# ADCduinoModule_Sensor_2.net
KiCad netlist of a schematic drawn in Altium Designer
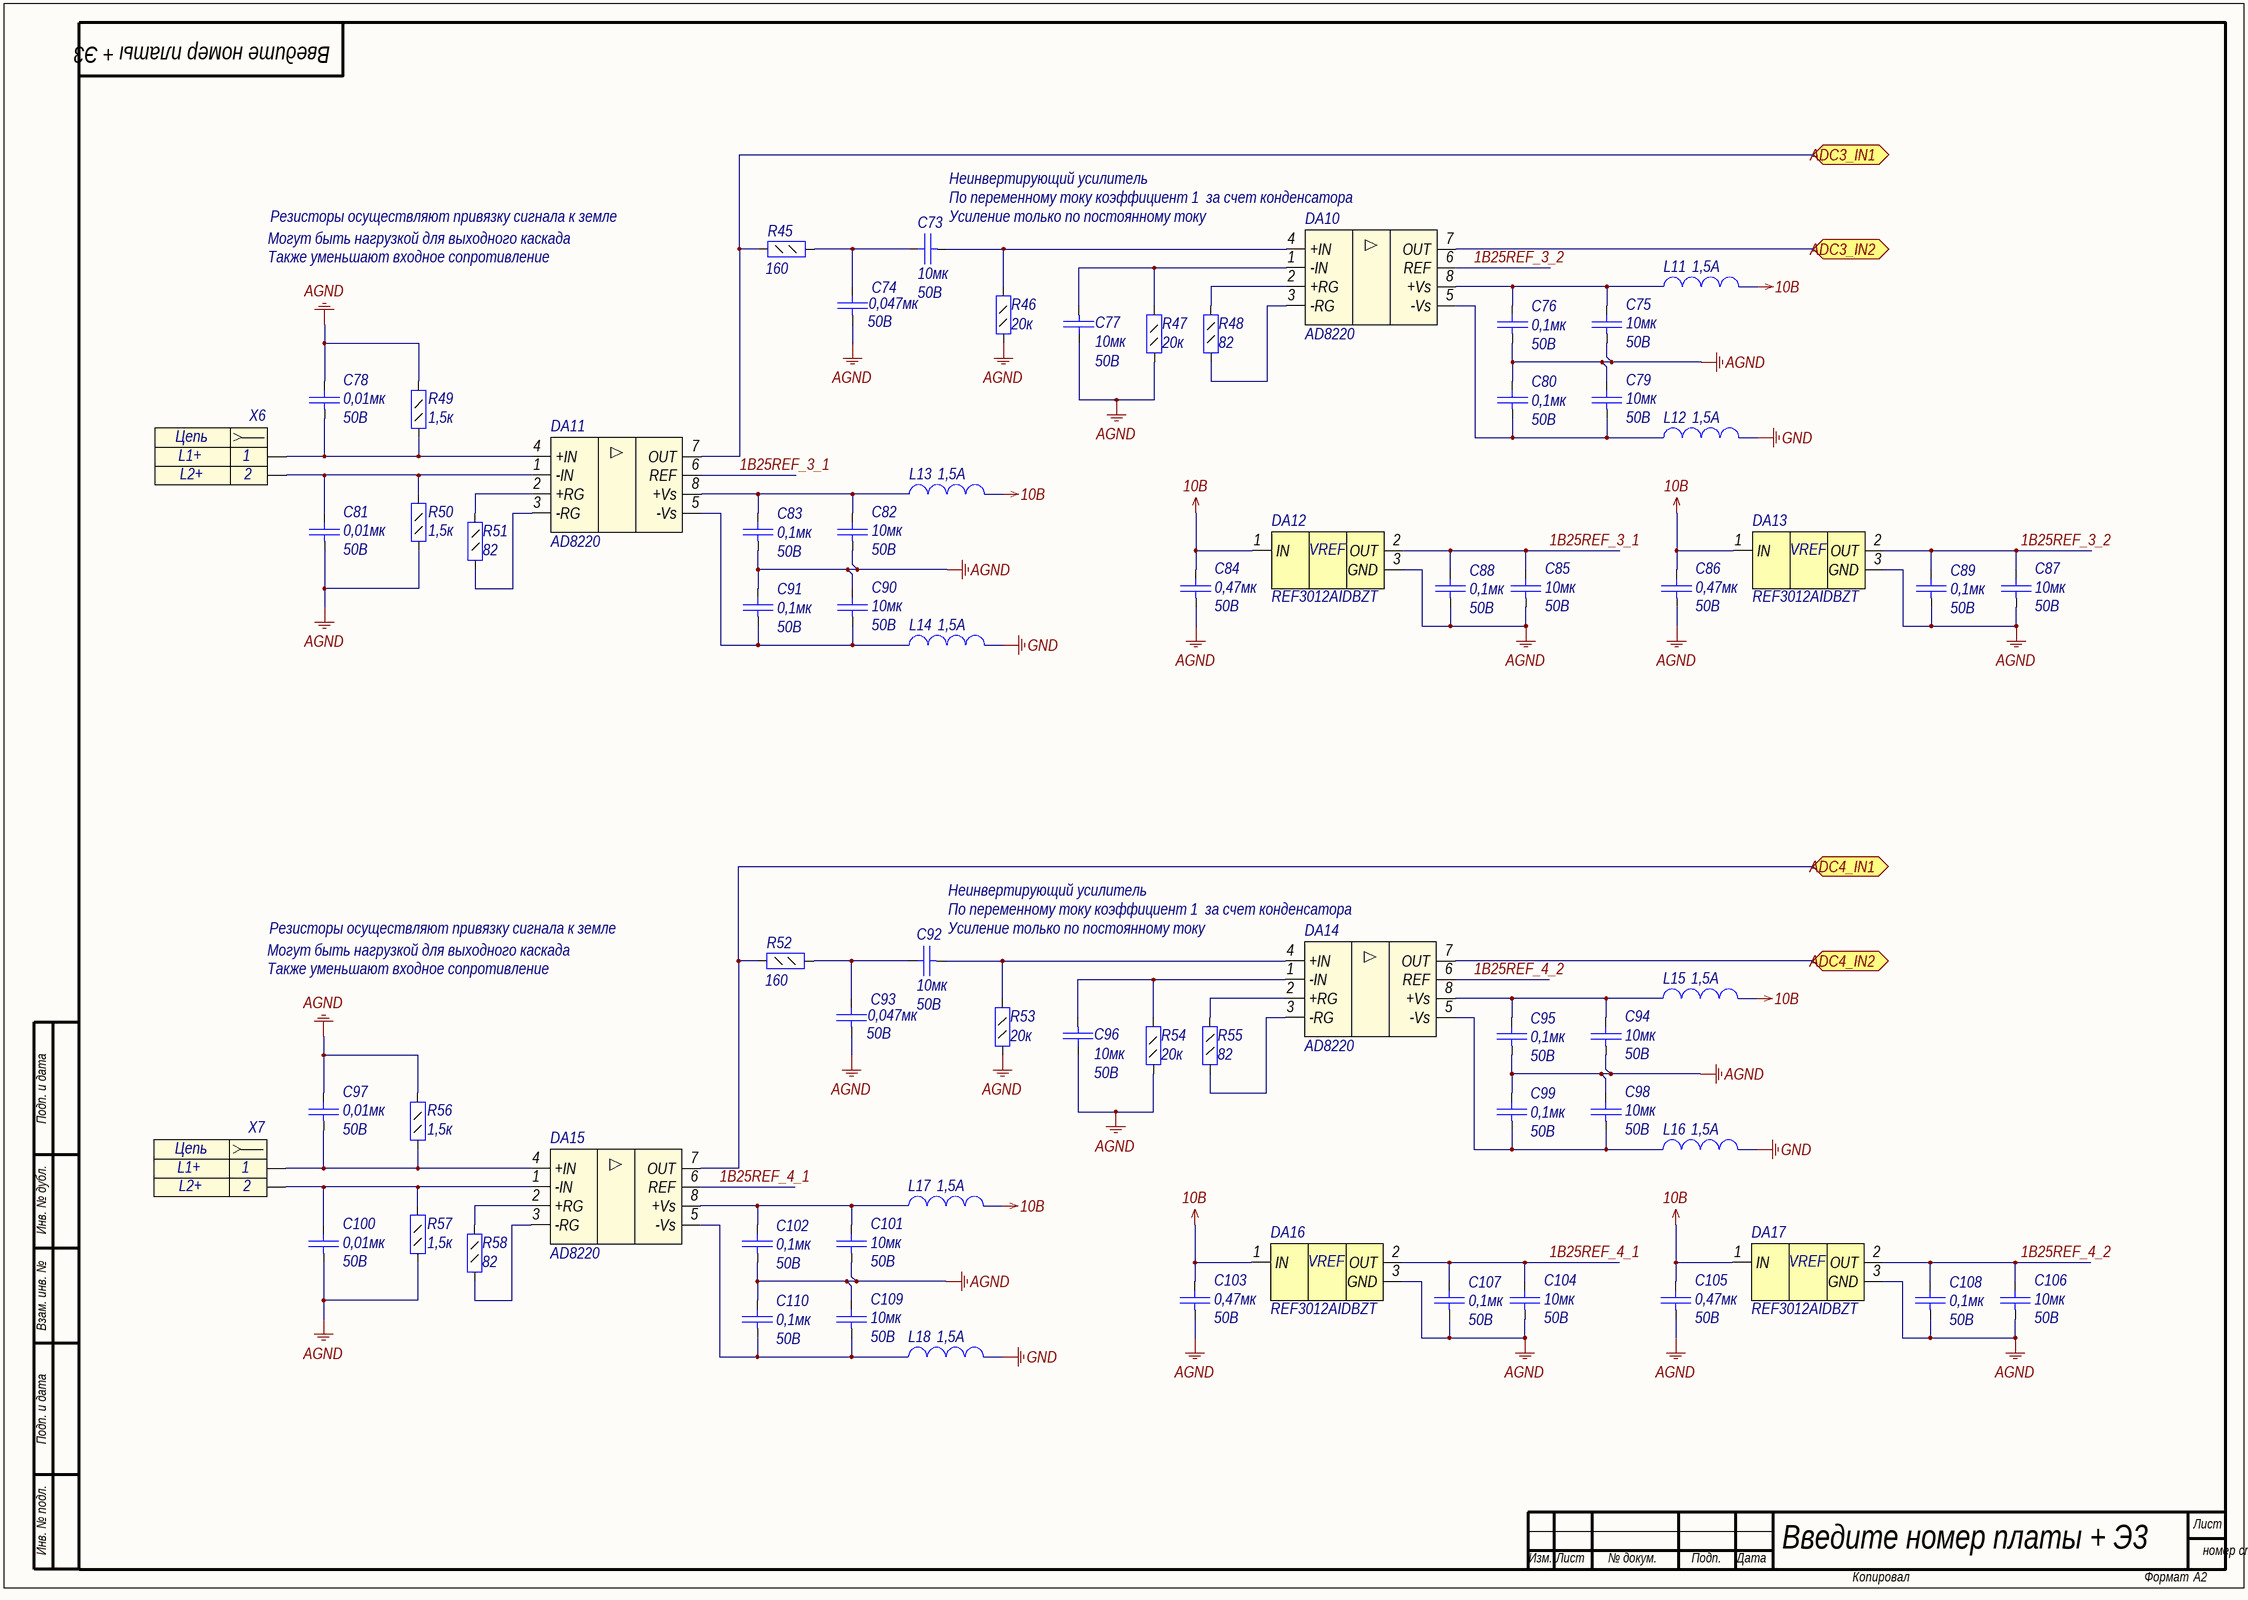
[diagram p0: ADCduinoModule_Sensor_2.SchDoc]

(export (version "E")
  (design (tool "Eeschema 10.0.6"))
  (components
    (comp (ref "C73")
      (value "10мк")
      (footprint "C1210")
      (description "Конденсатор")
      (fields
        (field (name "VOLTAGE") "50В")
        (field (name "PART NUMBER") "GRM32ER71H106K")
        (field (name "Comment") "Capacitor")
      )
      (libsource (lib "MOP44") (part "Capacitor"))
    )
    (comp (ref "C74")
      (value "0,047мк")
      (footprint "C0805")
      (description "Конденсатор")
      (fields
        (field (name "VOLTAGE") "50B")
        (field (name "PART NUMBER") "GRM21BR71H473K")
        (field (name "Comment") "Capacitor")
      )
      (libsource (lib "MOP44") (part "Capacitor"))
    )
    (comp (ref "C75")
      (value "10мк")
      (footprint "C1210")
      (description "Конденсатор")
      (fields
        (field (name "VOLTAGE") "50В")
        (field (name "PART NUMBER") "GRM32ER71H106K")
        (field (name "Comment") "Capacitor")
      )
      (libsource (lib "MOP44") (part "Capacitor"))
    )
    (comp (ref "C76")
      (value "0,1мк")
      (footprint "C0805")
      (description "Конденсатор")
      (fields
        (field (name "VOLTAGE") "50B")
        (field (name "PART NUMBER") "GRM21BR71H104K**")
        (field (name "Comment") "Capacitor")
      )
      (libsource (lib "MOP44") (part "Capacitor"))
    )
    (comp (ref "C77")
      (value "10мк")
      (footprint "C1210")
      (description "Конденсатор")
      (fields
        (field (name "VOLTAGE") "50В")
        (field (name "PART NUMBER") "GRM32ER71H106K")
        (field (name "Comment") "Capacitor")
      )
      (libsource (lib "MOP44") (part "Capacitor"))
    )
    (comp (ref "C78")
      (value "0,01мк")
      (footprint "C0805")
      (description "Конденсатор")
      (fields
        (field (name "VOLTAGE") "50B")
        (field (name "PART NUMBER") "GRM216R71H103K")
        (field (name "Comment") "Capacitor")
      )
      (libsource (lib "MOP44") (part "Capacitor"))
    )
    (comp (ref "C79")
      (value "10мк")
      (footprint "C1210")
      (description "Конденсатор")
      (fields
        (field (name "VOLTAGE") "50В")
        (field (name "PART NUMBER") "GRM32ER71H106K")
        (field (name "Comment") "Capacitor")
      )
      (libsource (lib "MOP44") (part "Capacitor"))
    )
    (comp (ref "C80")
      (value "0,1мк")
      (footprint "C0805")
      (description "Конденсатор")
      (fields
        (field (name "VOLTAGE") "50B")
        (field (name "PART NUMBER") "GRM21BR71H104K**")
        (field (name "Comment") "Capacitor")
      )
      (libsource (lib "MOP44") (part "Capacitor"))
    )
    (comp (ref "C81")
      (value "0,01мк")
      (footprint "C0805")
      (description "Конденсатор")
      (fields
        (field (name "VOLTAGE") "50B")
        (field (name "PART NUMBER") "GRM216R71H103K")
        (field (name "Comment") "Capacitor")
      )
      (libsource (lib "MOP44") (part "Capacitor"))
    )
    (comp (ref "C82")
      (value "10мк")
      (footprint "C1210")
      (description "Конденсатор")
      (fields
        (field (name "VOLTAGE") "50В")
        (field (name "PART NUMBER") "GRM32ER71H106K")
        (field (name "Comment") "Capacitor")
      )
      (libsource (lib "MOP44") (part "Capacitor"))
    )
    (comp (ref "C83")
      (value "0,1мк")
      (footprint "C0805")
      (description "Конденсатор")
      (fields
        (field (name "VOLTAGE") "50B")
        (field (name "PART NUMBER") "GRM21BR71H104K**")
        (field (name "Comment") "Capacitor")
      )
      (libsource (lib "MOP44") (part "Capacitor"))
    )
    (comp (ref "C84")
      (value "0,47мк")
      (footprint "C0805")
      (description "Конденсатор")
      (fields
        (field (name "VOLTAGE") "50B")
        (field (name "PART NUMBER") "GRM219R71C474K")
        (field (name "Comment") "Capacitor")
      )
      (libsource (lib "MOP44") (part "Capacitor"))
    )
    (comp (ref "C85")
      (value "10мк")
      (footprint "C1210")
      (description "Конденсатор")
      (fields
        (field (name "VOLTAGE") "50В")
        (field (name "PART NUMBER") "GRM32ER71H106K")
        (field (name "Comment") "Capacitor")
      )
      (libsource (lib "MOP44") (part "Capacitor"))
    )
    (comp (ref "C86")
      (value "0,47мк")
      (footprint "C0805")
      (description "Конденсатор")
      (fields
        (field (name "VOLTAGE") "50B")
        (field (name "PART NUMBER") "GRM219R71C474K")
        (field (name "Comment") "Capacitor")
      )
      (libsource (lib "MOP44") (part "Capacitor"))
    )
    (comp (ref "C87")
      (value "10мк")
      (footprint "C1210")
      (description "Конденсатор")
      (fields
        (field (name "VOLTAGE") "50В")
        (field (name "PART NUMBER") "GRM32ER71H106K")
        (field (name "Comment") "Capacitor")
      )
      (libsource (lib "MOP44") (part "Capacitor"))
    )
    (comp (ref "C88")
      (value "0,1мк")
      (footprint "C0805")
      (description "Конденсатор")
      (fields
        (field (name "VOLTAGE") "50B")
        (field (name "PART NUMBER") "GRM21BR71H104K**")
        (field (name "Comment") "Capacitor")
      )
      (libsource (lib "MOP44") (part "Capacitor"))
    )
    (comp (ref "C89")
      (value "0,1мк")
      (footprint "C0805")
      (description "Конденсатор")
      (fields
        (field (name "VOLTAGE") "50B")
        (field (name "PART NUMBER") "GRM21BR71H104K**")
        (field (name "Comment") "Capacitor")
      )
      (libsource (lib "MOP44") (part "Capacitor"))
    )
    (comp (ref "C90")
      (value "10мк")
      (footprint "C1210")
      (description "Конденсатор")
      (fields
        (field (name "VOLTAGE") "50В")
        (field (name "PART NUMBER") "GRM32ER71H106K")
        (field (name "Comment") "Capacitor")
      )
      (libsource (lib "MOP44") (part "Capacitor"))
    )
    (comp (ref "C91")
      (value "0,1мк")
      (footprint "C0805")
      (description "Конденсатор")
      (fields
        (field (name "VOLTAGE") "50B")
        (field (name "PART NUMBER") "GRM21BR71H104K**")
        (field (name "Comment") "Capacitor")
      )
      (libsource (lib "MOP44") (part "Capacitor"))
    )
    (comp (ref "C92")
      (value "10мк")
      (footprint "C1210")
      (description "Конденсатор")
      (fields
        (field (name "VOLTAGE") "50В")
        (field (name "PART NUMBER") "GRM32ER71H106K")
        (field (name "Comment") "Capacitor")
      )
      (libsource (lib "MOP44") (part "Capacitor"))
    )
    (comp (ref "C93")
      (value "0,047мк")
      (footprint "C0805")
      (description "Конденсатор")
      (fields
        (field (name "VOLTAGE") "50B")
        (field (name "PART NUMBER") "GRM21BR71H473K")
        (field (name "Comment") "Capacitor")
      )
      (libsource (lib "MOP44") (part "Capacitor"))
    )
    (comp (ref "C94")
      (value "10мк")
      (footprint "C1210")
      (description "Конденсатор")
      (fields
        (field (name "VOLTAGE") "50В")
        (field (name "PART NUMBER") "GRM32ER71H106K")
        (field (name "Comment") "Capacitor")
      )
      (libsource (lib "MOP44") (part "Capacitor"))
    )
    (comp (ref "C95")
      (value "0,1мк")
      (footprint "C0805")
      (description "Конденсатор")
      (fields
        (field (name "VOLTAGE") "50B")
        (field (name "PART NUMBER") "GRM21BR71H104K**")
        (field (name "Comment") "Capacitor")
      )
      (libsource (lib "MOP44") (part "Capacitor"))
    )
    (comp (ref "C96")
      (value "10мк")
      (footprint "C1210")
      (description "Конденсатор")
      (fields
        (field (name "VOLTAGE") "50В")
        (field (name "PART NUMBER") "GRM32ER71H106K")
        (field (name "Comment") "Capacitor")
      )
      (libsource (lib "") (part "Capacitor_1"))
    )
    (comp (ref "C97")
      (value "0,01мк")
      (footprint "C0805")
      (description "Конденсатор")
      (fields
        (field (name "VOLTAGE") "50B")
        (field (name "PART NUMBER") "GRM216R71H103K")
        (field (name "Comment") "Capacitor")
      )
      (libsource (lib "MOP44") (part "Capacitor"))
    )
    (comp (ref "C98")
      (value "10мк")
      (footprint "C1210")
      (description "Конденсатор")
      (fields
        (field (name "VOLTAGE") "50В")
        (field (name "PART NUMBER") "GRM32ER71H106K")
        (field (name "Comment") "Capacitor")
      )
      (libsource (lib "MOP44") (part "Capacitor"))
    )
    (comp (ref "C99")
      (value "0,1мк")
      (footprint "C0805")
      (description "Конденсатор")
      (fields
        (field (name "VOLTAGE") "50B")
        (field (name "PART NUMBER") "GRM21BR71H104K**")
        (field (name "Comment") "Capacitor")
      )
      (libsource (lib "MOP44") (part "Capacitor"))
    )
    (comp (ref "C100")
      (value "0,01мк")
      (footprint "C0805")
      (description "Конденсатор")
      (fields
        (field (name "VOLTAGE") "50B")
        (field (name "PART NUMBER") "GRM216R71H103K")
        (field (name "Comment") "Capacitor")
      )
      (libsource (lib "MOP44") (part "Capacitor"))
    )
    (comp (ref "C101")
      (value "10мк")
      (footprint "C1210")
      (description "Конденсатор")
      (fields
        (field (name "VOLTAGE") "50В")
        (field (name "PART NUMBER") "GRM32ER71H106K")
        (field (name "Comment") "Capacitor")
      )
      (libsource (lib "MOP44") (part "Capacitor"))
    )
    (comp (ref "C102")
      (value "0,1мк")
      (footprint "C0805")
      (description "Конденсатор")
      (fields
        (field (name "VOLTAGE") "50B")
        (field (name "PART NUMBER") "GRM21BR71H104K**")
        (field (name "Comment") "Capacitor")
      )
      (libsource (lib "MOP44") (part "Capacitor"))
    )
    (comp (ref "C103")
      (value "0,47мк")
      (footprint "C0805")
      (description "Конденсатор")
      (fields
        (field (name "VOLTAGE") "50B")
        (field (name "PART NUMBER") "GRM219R71C474K")
        (field (name "Comment") "Capacitor")
      )
      (libsource (lib "MOP44") (part "Capacitor"))
    )
    (comp (ref "C104")
      (value "10мк")
      (footprint "C1210")
      (description "Конденсатор")
      (fields
        (field (name "VOLTAGE") "50В")
        (field (name "PART NUMBER") "GRM32ER71H106K")
        (field (name "Comment") "Capacitor")
      )
      (libsource (lib "MOP44") (part "Capacitor"))
    )
    (comp (ref "C105")
      (value "0,47мк")
      (footprint "C0805")
      (description "Конденсатор")
      (fields
        (field (name "VOLTAGE") "50B")
        (field (name "PART NUMBER") "GRM219R71C474K")
        (field (name "Comment") "Capacitor")
      )
      (libsource (lib "MOP44") (part "Capacitor"))
    )
    (comp (ref "C106")
      (value "10мк")
      (footprint "C1210")
      (description "Конденсатор")
      (fields
        (field (name "VOLTAGE") "50В")
        (field (name "PART NUMBER") "GRM32ER71H106K")
        (field (name "Comment") "Capacitor")
      )
      (libsource (lib "MOP44") (part "Capacitor"))
    )
    (comp (ref "C107")
      (value "0,1мк")
      (footprint "C0805")
      (description "Конденсатор")
      (fields
        (field (name "VOLTAGE") "50B")
        (field (name "PART NUMBER") "GRM21BR71H104K**")
        (field (name "Comment") "Capacitor")
      )
      (libsource (lib "MOP44") (part "Capacitor"))
    )
    (comp (ref "C108")
      (value "0,1мк")
      (footprint "C0805")
      (description "Конденсатор")
      (fields
        (field (name "VOLTAGE") "50B")
        (field (name "PART NUMBER") "GRM21BR71H104K**")
        (field (name "Comment") "Capacitor")
      )
      (libsource (lib "MOP44") (part "Capacitor"))
    )
    (comp (ref "C109")
      (value "10мк")
      (footprint "C1210")
      (description "Конденсатор")
      (fields
        (field (name "VOLTAGE") "50В")
        (field (name "PART NUMBER") "GRM32ER71H106K")
        (field (name "Comment") "Capacitor")
      )
      (libsource (lib "MOP44") (part "Capacitor"))
    )
    (comp (ref "C110")
      (value "0,1мк")
      (footprint "C0805")
      (description "Конденсатор")
      (fields
        (field (name "VOLTAGE") "50B")
        (field (name "PART NUMBER") "GRM21BR71H104K**")
        (field (name "Comment") "Capacitor")
      )
      (libsource (lib "MOP44") (part "Capacitor"))
    )
    (comp (ref "DA10")
      (value "AD8220")
      (footprint "MSOP8")
      (description "JFET Input Instrumentation Amplifier")
      (fields (field (name "PART NUMBER") "AD8220ARMZ"))
      (libsource (lib "MOP44") (part "AD8220"))
    )
    (comp (ref "DA11")
      (value "AD8220")
      (footprint "MSOP8")
      (description "JFET Input Instrumentation Amplifier")
      (fields (field (name "PART NUMBER") "AD8220ARMZ"))
      (libsource (lib "MOP44") (part "AD8220"))
    )
    (comp (ref "DA12")
      (value "REF30xx")
      (footprint "SOT23-3")
      (description "CMOS Voltage Reference")
      (fields (field (name "PART NUMBER") "REF3012AIDBZT") (field (name "MANUFACTURER") "Texas Instruments"))
      (libsource (lib "MOP44") (part "REF30xx"))
    )
    (comp (ref "DA13")
      (value "REF30xx")
      (footprint "SOT23-3")
      (description "CMOS Voltage Reference")
      (fields (field (name "PART NUMBER") "REF3012AIDBZT") (field (name "MANUFACTURER") "Texas Instruments"))
      (libsource (lib "MOP44") (part "REF30xx"))
    )
    (comp (ref "DA14")
      (value "AD8220")
      (footprint "MSOP8")
      (description "JFET Input Instrumentation Amplifier")
      (fields (field (name "PART NUMBER") "AD8220ARMZ"))
      (libsource (lib "") (part "AD8220_1"))
    )
    (comp (ref "DA15")
      (value "AD8220")
      (footprint "MSOP8")
      (description "JFET Input Instrumentation Amplifier")
      (fields (field (name "PART NUMBER") "AD8220ARMZ"))
      (libsource (lib "MOP44") (part "AD8220"))
    )
    (comp (ref "DA16")
      (value "REF30xx")
      (footprint "SOT23-3")
      (description "CMOS Voltage Reference")
      (fields (field (name "PART NUMBER") "REF3012AIDBZT") (field (name "MANUFACTURER") "Texas Instruments"))
      (libsource (lib "MOP44") (part "REF30xx"))
    )
    (comp (ref "DA17")
      (value "REF30xx")
      (footprint "SOT23-3")
      (description "CMOS Voltage Reference")
      (fields (field (name "PART NUMBER") "REF3012AIDBZT") (field (name "MANUFACTURER") "Texas Instruments"))
      (libsource (lib "MOP44") (part "REF30xx"))
    )
    (comp (ref "L11")
      (value "Inductor")
      (footprint "L0603")
      (description "EMI Suppression Filter")
      (fields (field (name "RATED CURRENT") "1,5A") (field (name "PART NUMBER") "BLM18PG181SN1D"))
      (libsource (lib "MOP44") (part "Inductor"))
    )
    (comp (ref "L12")
      (value "Inductor")
      (footprint "L0603")
      (description "EMI Suppression Filter")
      (fields (field (name "RATED CURRENT") "1,5A") (field (name "PART NUMBER") "BLM18PG181SN1D"))
      (libsource (lib "MOP44") (part "Inductor"))
    )
    (comp (ref "L13")
      (value "Inductor")
      (footprint "L0603")
      (description "EMI Suppression Filter")
      (fields (field (name "RATED CURRENT") "1,5A") (field (name "PART NUMBER") "BLM18PG181SN1D"))
      (libsource (lib "MOP44") (part "Inductor"))
    )
    (comp (ref "L14")
      (value "Inductor")
      (footprint "L0603")
      (description "EMI Suppression Filter")
      (fields (field (name "RATED CURRENT") "1,5A") (field (name "PART NUMBER") "BLM18PG181SN1D"))
      (libsource (lib "MOP44") (part "Inductor"))
    )
    (comp (ref "L15")
      (value "Inductor")
      (footprint "L0603")
      (description "EMI Suppression Filter")
      (fields (field (name "RATED CURRENT") "1,5A") (field (name "PART NUMBER") "BLM18PG181SN1D"))
      (libsource (lib "MOP44") (part "Inductor"))
    )
    (comp (ref "L16")
      (value "Inductor")
      (footprint "L0603")
      (description "EMI Suppression Filter")
      (fields (field (name "RATED CURRENT") "1,5A") (field (name "PART NUMBER") "BLM18PG181SN1D"))
      (libsource (lib "MOP44") (part "Inductor"))
    )
    (comp (ref "L17")
      (value "Inductor")
      (footprint "L0603")
      (description "EMI Suppression Filter")
      (fields (field (name "RATED CURRENT") "1,5A") (field (name "PART NUMBER") "BLM18PG181SN1D"))
      (libsource (lib "MOP44") (part "Inductor"))
    )
    (comp (ref "L18")
      (value "Inductor")
      (footprint "L0603")
      (description "EMI Suppression Filter")
      (fields (field (name "RATED CURRENT") "1,5A") (field (name "PART NUMBER") "BLM18PG181SN1D"))
      (libsource (lib "MOP44") (part "Inductor"))
    )
    (comp (ref "R45")
      (value "160")
      (footprint "R0805")
      (description "Резистор")
      (fields (field (name "PART NUMBER") "RC0805FR-07160RL") (field (name "POWER") "0,125Вт"))
      (libsource (lib "") (part "Resistor_0,125Вт_1"))
    )
    (comp (ref "R46")
      (value "20к")
      (footprint "R0805")
      (description "Резистор")
      (fields (field (name "PART NUMBER") "RC0805FR-0720KL") (field (name "POWER") "0,125Вт"))
      (libsource (lib "") (part "Resistor_0,125Вт_2"))
    )
    (comp (ref "R47")
      (value "20к")
      (footprint "R0805")
      (description "Резистор")
      (fields (field (name "PART NUMBER") "RC0805FR-0720KL") (field (name "POWER") "0,125Вт"))
      (libsource (lib "") (part "Resistor_0,125Вт_2"))
    )
    (comp (ref "R48")
      (value "82")
      (footprint "R0805")
      (description "Резистор")
      (fields (field (name "PART NUMBER") "RC0805FR-0782RL") (field (name "POWER") "0,125Вт"))
      (libsource (lib "MOP44") (part "Resistor_0,125Вт"))
    )
    (comp (ref "R49")
      (value "1,5к")
      (footprint "R0805")
      (description "Резистор")
      (fields (field (name "PART NUMBER") "RC0805FR-071K5") (field (name "POWER") "0,125Вт"))
      (libsource (lib "") (part "Resistor_0,125Вт_2"))
    )
    (comp (ref "R50")
      (value "1,5к")
      (footprint "R0805")
      (description "Резистор")
      (fields (field (name "PART NUMBER") "RC0805FR-071K5") (field (name "POWER") "0,125Вт"))
      (libsource (lib "") (part "Resistor_0,125Вт_2"))
    )
    (comp (ref "R51")
      (value "82")
      (footprint "R0805")
      (description "Резистор")
      (fields (field (name "PART NUMBER") "RC0805FR-0782RL") (field (name "POWER") "0,125Вт"))
      (libsource (lib "MOP44") (part "Resistor_0,125Вт"))
    )
    (comp (ref "R52")
      (value "160")
      (footprint "R0805")
      (description "Резистор")
      (fields (field (name "PART NUMBER") "RC0805FR-07160RL") (field (name "POWER") "0,125Вт"))
      (libsource (lib "") (part "Resistor_0,125Вт_1"))
    )
    (comp (ref "R53")
      (value "20к")
      (footprint "R0805")
      (description "Резистор")
      (fields (field (name "PART NUMBER") "RC0805FR-0720KL") (field (name "POWER") "0,125Вт"))
      (libsource (lib "") (part "Resistor_0,125Вт_2"))
    )
    (comp (ref "R54")
      (value "20к")
      (footprint "R0805")
      (description "Резистор")
      (fields (field (name "PART NUMBER") "RC0805FR-0720KL") (field (name "POWER") "0,125Вт"))
      (libsource (lib "") (part "Resistor_0,125Вт_4"))
    )
    (comp (ref "R55")
      (value "82")
      (footprint "R0805")
      (description "Резистор")
      (fields (field (name "PART NUMBER") "RC0805FR-0782RL") (field (name "POWER") "0,125Вт"))
      (libsource (lib "") (part "Resistor_0,125Вт_3"))
    )
    (comp (ref "R56")
      (value "1,5к")
      (footprint "R0805")
      (description "Резистор")
      (fields (field (name "PART NUMBER") "RC0805FR-071K5") (field (name "POWER") "0,125Вт"))
      (libsource (lib "") (part "Resistor_0,125Вт_2"))
    )
    (comp (ref "R57")
      (value "1,5к")
      (footprint "R0805")
      (description "Резистор")
      (fields (field (name "PART NUMBER") "RC0805FR-071K5") (field (name "POWER") "0,125Вт"))
      (libsource (lib "") (part "Resistor_0,125Вт_2"))
    )
    (comp (ref "R58")
      (value "82")
      (footprint "R0805")
      (description "Резистор")
      (fields (field (name "PART NUMBER") "RC0805FR-0782RL") (field (name "POWER") "0,125Вт"))
      (libsource (lib "MOP44") (part "Resistor_0,125Вт"))
    )
    (comp (ref "X6")
      (value "Header_2_sct")
      (footprint "TAB_2PAD")
      (description "Разъем - 2 конт. розетка")
      (libsource (lib "MOP44") (part "Header_2_sct"))
    )
    (comp (ref "X7")
      (value "Header_2_sct")
      (footprint "TAB_2PAD")
      (description "Разъем - 2 конт. розетка")
      (libsource (lib "") (part "Header_2_sct_1"))
    )
  )
  (nets
    (net (code "1") (name "/1B25REF_3_1") (class "Default")
      (node (ref "C85") (pin "2") (pinfunction "2_2") (pintype "passive"))
      (node (ref "C88") (pin "2") (pinfunction "2_2") (pintype "passive"))
      (node (ref "DA11") (pin "6") (pinfunction "REF_6") (pintype "passive"))
      (node (ref "DA12") (pin "2") (pinfunction "OUT_2") (pintype "passive"))
    )
    (net (code "2") (name "/1B25REF_3_2") (class "Default")
      (node (ref "C87") (pin "2") (pinfunction "2_2") (pintype "passive"))
      (node (ref "C89") (pin "2") (pinfunction "2_2") (pintype "passive"))
      (node (ref "DA10") (pin "6") (pinfunction "REF_6") (pintype "passive"))
      (node (ref "DA13") (pin "2") (pinfunction "OUT_2") (pintype "passive"))
    )
    (net (code "3") (name "/1B25REF_4_1") (class "Default")
      (node (ref "C104") (pin "2") (pinfunction "2_2") (pintype "passive"))
      (node (ref "C107") (pin "2") (pinfunction "2_2") (pintype "passive"))
      (node (ref "DA15") (pin "6") (pinfunction "REF_6") (pintype "passive"))
      (node (ref "DA16") (pin "2") (pinfunction "OUT_2") (pintype "passive"))
    )
    (net (code "4") (name "/1B25REF_4_2") (class "Default")
      (node (ref "C106") (pin "2") (pinfunction "2_2") (pintype "passive"))
      (node (ref "C108") (pin "2") (pinfunction "2_2") (pintype "passive"))
      (node (ref "DA14") (pin "6") (pinfunction "REF_6") (pintype "passive"))
      (node (ref "DA17") (pin "2") (pinfunction "OUT_2") (pintype "passive"))
    )
    (net (code "5") (name "/ADC3_IN1") (class "Default")
      (node (ref "DA11") (pin "7") (pinfunction "OUT_7") (pintype "passive"))
      (node (ref "R45") (pin "1") (pinfunction "1_1") (pintype "passive"))
    )
    (net (code "6") (name "/ADC3_IN2") (class "Default")
      (node (ref "DA10") (pin "7") (pinfunction "OUT_7") (pintype "passive"))
    )
    (net (code "7") (name "/ADC4_IN1") (class "Default")
      (node (ref "DA15") (pin "7") (pinfunction "OUT_7") (pintype "passive"))
      (node (ref "R52") (pin "1") (pinfunction "1_1") (pintype "passive"))
    )
    (net (code "8") (name "/ADC4_IN2") (class "Default")
      (node (ref "DA14") (pin "7") (pinfunction "OUT_7") (pintype "passive"))
    )
    (net (code "9") (name "10B") (class "Default")
      (node (ref "C103") (pin "2") (pinfunction "2_2") (pintype "passive"))
      (node (ref "C105") (pin "2") (pinfunction "2_2") (pintype "passive"))
      (node (ref "C84") (pin "2") (pinfunction "2_2") (pintype "passive"))
      (node (ref "C86") (pin "2") (pinfunction "2_2") (pintype "passive"))
      (node (ref "DA12") (pin "1") (pinfunction "IN_1") (pintype "passive"))
      (node (ref "DA13") (pin "1") (pinfunction "IN_1") (pintype "passive"))
      (node (ref "DA16") (pin "1") (pinfunction "IN_1") (pintype "passive"))
      (node (ref "DA17") (pin "1") (pinfunction "IN_1") (pintype "passive"))
      (node (ref "L11") (pin "2") (pinfunction "2_2") (pintype "passive"))
      (node (ref "L13") (pin "2") (pinfunction "2_2") (pintype "passive"))
      (node (ref "L15") (pin "2") (pinfunction "2_2") (pintype "passive"))
      (node (ref "L17") (pin "2") (pinfunction "2_2") (pintype "passive"))
    )
    (net (code "10") (name "AGND") (class "Default")
      (node (ref "C100") (pin "1") (pinfunction "1_1") (pintype "passive"))
      (node (ref "C101") (pin "1") (pinfunction "1_1") (pintype "passive"))
      (node (ref "C102") (pin "1") (pinfunction "1_1") (pintype "passive"))
      (node (ref "C103") (pin "1") (pinfunction "1_1") (pintype "passive"))
      (node (ref "C104") (pin "1") (pinfunction "1_1") (pintype "passive"))
      (node (ref "C105") (pin "1") (pinfunction "1_1") (pintype "passive"))
      (node (ref "C106") (pin "1") (pinfunction "1_1") (pintype "passive"))
      (node (ref "C107") (pin "1") (pinfunction "1_1") (pintype "passive"))
      (node (ref "C108") (pin "1") (pinfunction "1_1") (pintype "passive"))
      (node (ref "C109") (pin "2") (pinfunction "2_2") (pintype "passive"))
      (node (ref "C110") (pin "2") (pinfunction "2_2") (pintype "passive"))
      (node (ref "C74") (pin "1") (pinfunction "1_1") (pintype "passive"))
      (node (ref "C75") (pin "1") (pinfunction "1_1") (pintype "passive"))
      (node (ref "C76") (pin "1") (pinfunction "1_1") (pintype "passive"))
      (node (ref "C77") (pin "2") (pinfunction "2_2") (pintype "passive"))
      (node (ref "C78") (pin "2") (pinfunction "2_2") (pintype "passive"))
      (node (ref "C79") (pin "2") (pinfunction "2_2") (pintype "passive"))
      (node (ref "C80") (pin "2") (pinfunction "2_2") (pintype "passive"))
      (node (ref "C81") (pin "1") (pinfunction "1_1") (pintype "passive"))
      (node (ref "C82") (pin "1") (pinfunction "1_1") (pintype "passive"))
      (node (ref "C83") (pin "1") (pinfunction "1_1") (pintype "passive"))
      (node (ref "C84") (pin "1") (pinfunction "1_1") (pintype "passive"))
      (node (ref "C85") (pin "1") (pinfunction "1_1") (pintype "passive"))
      (node (ref "C86") (pin "1") (pinfunction "1_1") (pintype "passive"))
      (node (ref "C87") (pin "1") (pinfunction "1_1") (pintype "passive"))
      (node (ref "C88") (pin "1") (pinfunction "1_1") (pintype "passive"))
      (node (ref "C89") (pin "1") (pinfunction "1_1") (pintype "passive"))
      (node (ref "C90") (pin "2") (pinfunction "2_2") (pintype "passive"))
      (node (ref "C91") (pin "2") (pinfunction "2_2") (pintype "passive"))
      (node (ref "C93") (pin "1") (pinfunction "1_1") (pintype "passive"))
      (node (ref "C94") (pin "1") (pinfunction "1_1") (pintype "passive"))
      (node (ref "C95") (pin "1") (pinfunction "1_1") (pintype "passive"))
      (node (ref "C96") (pin "2") (pinfunction "2_2") (pintype "passive"))
      (node (ref "C97") (pin "2") (pinfunction "2_2") (pintype "passive"))
      (node (ref "C98") (pin "2") (pinfunction "2_2") (pintype "passive"))
      (node (ref "C99") (pin "2") (pinfunction "2_2") (pintype "passive"))
      (node (ref "DA12") (pin "3") (pinfunction "GND_3") (pintype "passive"))
      (node (ref "DA13") (pin "3") (pinfunction "GND_3") (pintype "passive"))
      (node (ref "DA16") (pin "3") (pinfunction "GND_3") (pintype "passive"))
      (node (ref "DA17") (pin "3") (pinfunction "GND_3") (pintype "passive"))
      (node (ref "R46") (pin "1") (pinfunction "1_1") (pintype "passive"))
      (node (ref "R47") (pin "1") (pinfunction "1_1") (pintype "passive"))
      (node (ref "R49") (pin "2") (pinfunction "2_2") (pintype "passive"))
      (node (ref "R50") (pin "1") (pinfunction "1_1") (pintype "passive"))
      (node (ref "R53") (pin "1") (pinfunction "1_1") (pintype "passive"))
      (node (ref "R54") (pin "1") (pinfunction "1_1") (pintype "passive"))
      (node (ref "R56") (pin "2") (pinfunction "2_2") (pintype "passive"))
      (node (ref "R57") (pin "1") (pinfunction "1_1") (pintype "passive"))
    )
    (net (code "11") (name "GND") (class "Default")
      (node (ref "L12") (pin "2") (pinfunction "2_2") (pintype "passive"))
      (node (ref "L14") (pin "2") (pinfunction "2_2") (pintype "passive"))
      (node (ref "L16") (pin "2") (pinfunction "2_2") (pintype "passive"))
      (node (ref "L18") (pin "2") (pinfunction "2_2") (pintype "passive"))
    )
    (net (code "12") (name "Net-(C73-Pad2)") (class "Default")
      (node (ref "C73") (pin "2") (pinfunction "2_2") (pintype "passive"))
      (node (ref "C74") (pin "2") (pinfunction "2_2") (pintype "passive"))
      (node (ref "R45") (pin "2") (pinfunction "2_2") (pintype "passive"))
    )
    (net (code "13") (name "Net-(C92-Pad2)") (class "Default")
      (node (ref "C92") (pin "2") (pinfunction "2_2") (pintype "passive"))
      (node (ref "C93") (pin "2") (pinfunction "2_2") (pintype "passive"))
      (node (ref "R52") (pin "2") (pinfunction "2_2") (pintype "passive"))
    )
    (net (code "14") (name "Net-(DA10-+IN)") (class "Default")
      (node (ref "C73") (pin "1") (pinfunction "1_1") (pintype "passive"))
      (node (ref "DA10") (pin "4") (pinfunction "+IN_4") (pintype "passive"))
      (node (ref "R46") (pin "2") (pinfunction "2_2") (pintype "passive"))
    )
    (net (code "15") (name "Net-(DA10-+RG)") (class "Default")
      (node (ref "DA10") (pin "2") (pinfunction "+RG_2") (pintype "passive"))
      (node (ref "R48") (pin "1") (pinfunction "1_1") (pintype "passive"))
    )
    (net (code "16") (name "Net-(DA10-+Vs)") (class "Default")
      (node (ref "C75") (pin "2") (pinfunction "2_2") (pintype "passive"))
      (node (ref "C76") (pin "2") (pinfunction "2_2") (pintype "passive"))
      (node (ref "DA10") (pin "8") (pinfunction "+Vs_8") (pintype "passive"))
      (node (ref "L11") (pin "1") (pinfunction "1_1") (pintype "passive"))
    )
    (net (code "17") (name "Net-(DA10--IN)") (class "Default")
      (node (ref "C77") (pin "1") (pinfunction "1_1") (pintype "passive"))
      (node (ref "DA10") (pin "1") (pinfunction "-IN_1") (pintype "passive"))
      (node (ref "R47") (pin "2") (pinfunction "2_2") (pintype "passive"))
    )
    (net (code "18") (name "Net-(DA10--RG)") (class "Default")
      (node (ref "DA10") (pin "3") (pinfunction "-RG_3") (pintype "passive"))
      (node (ref "R48") (pin "2") (pinfunction "2_2") (pintype "passive"))
    )
    (net (code "19") (name "Net-(DA10--Vs)") (class "Default")
      (node (ref "C79") (pin "1") (pinfunction "1_1") (pintype "passive"))
      (node (ref "C80") (pin "1") (pinfunction "1_1") (pintype "passive"))
      (node (ref "DA10") (pin "5") (pinfunction "-Vs_5") (pintype "passive"))
      (node (ref "L12") (pin "1") (pinfunction "1_1") (pintype "passive"))
    )
    (net (code "20") (name "Net-(DA11-+IN)") (class "Default")
      (node (ref "C78") (pin "1") (pinfunction "1_1") (pintype "passive"))
      (node (ref "DA11") (pin "4") (pinfunction "+IN_4") (pintype "passive"))
      (node (ref "R49") (pin "1") (pinfunction "1_1") (pintype "passive"))
      (node (ref "X6") (pin "1") (pinfunction "1_1") (pintype "passive"))
    )
    (net (code "21") (name "Net-(DA11-+RG)") (class "Default")
      (node (ref "DA11") (pin "2") (pinfunction "+RG_2") (pintype "passive"))
      (node (ref "R51") (pin "1") (pinfunction "1_1") (pintype "passive"))
    )
    (net (code "22") (name "Net-(DA11-+Vs)") (class "Default")
      (node (ref "C82") (pin "2") (pinfunction "2_2") (pintype "passive"))
      (node (ref "C83") (pin "2") (pinfunction "2_2") (pintype "passive"))
      (node (ref "DA11") (pin "8") (pinfunction "+Vs_8") (pintype "passive"))
      (node (ref "L13") (pin "1") (pinfunction "1_1") (pintype "passive"))
    )
    (net (code "23") (name "Net-(DA11--IN)") (class "Default")
      (node (ref "C81") (pin "2") (pinfunction "2_2") (pintype "passive"))
      (node (ref "DA11") (pin "1") (pinfunction "-IN_1") (pintype "passive"))
      (node (ref "R50") (pin "2") (pinfunction "2_2") (pintype "passive"))
      (node (ref "X6") (pin "2") (pinfunction "2_2") (pintype "passive"))
    )
    (net (code "24") (name "Net-(DA11--RG)") (class "Default")
      (node (ref "DA11") (pin "3") (pinfunction "-RG_3") (pintype "passive"))
      (node (ref "R51") (pin "2") (pinfunction "2_2") (pintype "passive"))
    )
    (net (code "25") (name "Net-(DA11--Vs)") (class "Default")
      (node (ref "C90") (pin "1") (pinfunction "1_1") (pintype "passive"))
      (node (ref "C91") (pin "1") (pinfunction "1_1") (pintype "passive"))
      (node (ref "DA11") (pin "5") (pinfunction "-Vs_5") (pintype "passive"))
      (node (ref "L14") (pin "1") (pinfunction "1_1") (pintype "passive"))
    )
    (net (code "26") (name "Net-(DA14-+IN)") (class "Default")
      (node (ref "C92") (pin "1") (pinfunction "1_1") (pintype "passive"))
      (node (ref "DA14") (pin "4") (pinfunction "+IN_4") (pintype "passive"))
      (node (ref "R53") (pin "2") (pinfunction "2_2") (pintype "passive"))
    )
    (net (code "27") (name "Net-(DA14-+RG)") (class "Default")
      (node (ref "DA14") (pin "2") (pinfunction "+RG_2") (pintype "passive"))
      (node (ref "R55") (pin "1") (pinfunction "1_1") (pintype "passive"))
    )
    (net (code "28") (name "Net-(DA14-+Vs)") (class "Default")
      (node (ref "C94") (pin "2") (pinfunction "2_2") (pintype "passive"))
      (node (ref "C95") (pin "2") (pinfunction "2_2") (pintype "passive"))
      (node (ref "DA14") (pin "8") (pinfunction "+Vs_8") (pintype "passive"))
      (node (ref "L15") (pin "1") (pinfunction "1_1") (pintype "passive"))
    )
    (net (code "29") (name "Net-(DA14--IN)") (class "Default")
      (node (ref "C96") (pin "1") (pinfunction "1_1") (pintype "passive"))
      (node (ref "DA14") (pin "1") (pinfunction "-IN_1") (pintype "passive"))
      (node (ref "R54") (pin "2") (pinfunction "2_2") (pintype "passive"))
    )
    (net (code "30") (name "Net-(DA14--RG)") (class "Default")
      (node (ref "DA14") (pin "3") (pinfunction "-RG_3") (pintype "passive"))
      (node (ref "R55") (pin "2") (pinfunction "2_2") (pintype "passive"))
    )
    (net (code "31") (name "Net-(DA14--Vs)") (class "Default")
      (node (ref "C98") (pin "1") (pinfunction "1_1") (pintype "passive"))
      (node (ref "C99") (pin "1") (pinfunction "1_1") (pintype "passive"))
      (node (ref "DA14") (pin "5") (pinfunction "-Vs_5") (pintype "passive"))
      (node (ref "L16") (pin "1") (pinfunction "1_1") (pintype "passive"))
    )
    (net (code "32") (name "Net-(DA15-+IN)") (class "Default")
      (node (ref "C97") (pin "1") (pinfunction "1_1") (pintype "passive"))
      (node (ref "DA15") (pin "4") (pinfunction "+IN_4") (pintype "passive"))
      (node (ref "R56") (pin "1") (pinfunction "1_1") (pintype "passive"))
      (node (ref "X7") (pin "1") (pinfunction "1_1") (pintype "passive"))
    )
    (net (code "33") (name "Net-(DA15-+RG)") (class "Default")
      (node (ref "DA15") (pin "2") (pinfunction "+RG_2") (pintype "passive"))
      (node (ref "R58") (pin "1") (pinfunction "1_1") (pintype "passive"))
    )
    (net (code "34") (name "Net-(DA15-+Vs)") (class "Default")
      (node (ref "C101") (pin "2") (pinfunction "2_2") (pintype "passive"))
      (node (ref "C102") (pin "2") (pinfunction "2_2") (pintype "passive"))
      (node (ref "DA15") (pin "8") (pinfunction "+Vs_8") (pintype "passive"))
      (node (ref "L17") (pin "1") (pinfunction "1_1") (pintype "passive"))
    )
    (net (code "35") (name "Net-(DA15--IN)") (class "Default")
      (node (ref "C100") (pin "2") (pinfunction "2_2") (pintype "passive"))
      (node (ref "DA15") (pin "1") (pinfunction "-IN_1") (pintype "passive"))
      (node (ref "R57") (pin "2") (pinfunction "2_2") (pintype "passive"))
      (node (ref "X7") (pin "2") (pinfunction "2_2") (pintype "passive"))
    )
    (net (code "36") (name "Net-(DA15--RG)") (class "Default")
      (node (ref "DA15") (pin "3") (pinfunction "-RG_3") (pintype "passive"))
      (node (ref "R58") (pin "2") (pinfunction "2_2") (pintype "passive"))
    )
    (net (code "37") (name "Net-(DA15--Vs)") (class "Default")
      (node (ref "C109") (pin "1") (pinfunction "1_1") (pintype "passive"))
      (node (ref "C110") (pin "1") (pinfunction "1_1") (pintype "passive"))
      (node (ref "DA15") (pin "5") (pinfunction "-Vs_5") (pintype "passive"))
      (node (ref "L18") (pin "1") (pinfunction "1_1") (pintype "passive"))
    )
  )
)
